# VL53L0X_ToF_Sensor.net
KiCad netlist of a schematic drawn in EAGLE
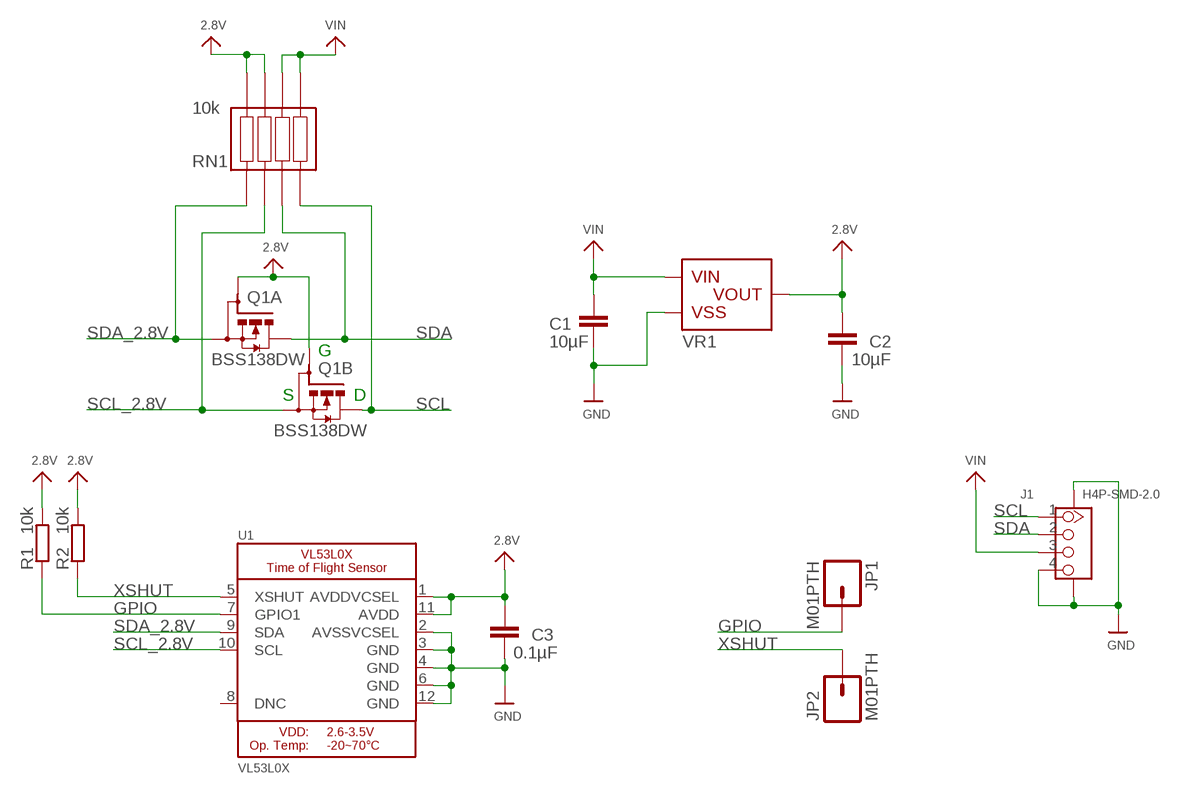
[diagram p0: schematic, sheet 1]

(export (version "E")
  (design (tool "Eeschema 10.0.6"))
  (components
    (comp (ref "C1")
      (value "10µF")
      (footprint "eagle-import:C0603")
      (libsource (lib "eagle-import") (part "C-EUC0603"))
    )
    (comp (ref "C2")
      (value "10µF")
      (footprint "eagle-import:C0603")
      (libsource (lib "eagle-import") (part "C-EUC0603"))
    )
    (comp (ref "C3")
      (value "0.1µF")
      (footprint "eagle-import:C0603")
      (libsource (lib "eagle-import") (part "C-EUC0603"))
    )
    (comp (ref "J1")
      (value "H4P-SMD-2.0")
      (footprint "eagle-import:HW4-SMD-2.0")
      (libsource (lib "eagle-import") (part "GROVE-CONNECTOR-4PIN"))
    )
    (comp (ref "JP1")
      (value "M01PTH")
      (footprint "eagle-import:1X01")
      (libsource (lib "eagle-import") (part "M01PTH"))
    )
    (comp (ref "JP2")
      (value "M01PTH")
      (footprint "eagle-import:1X01")
      (libsource (lib "eagle-import") (part "M01PTH"))
    )
    (comp (ref "Q1")
      (value "BSS138DW")
      (footprint "eagle-import:SOT363")
      (fields (field (name "MF") "ON SEMICONDUCTOR") (field (name "MPN") "NTJD5121NT1G"))
      (libsource (lib "eagle-import") (part "BSS138DW"))
    )
    (comp (ref "R1")
      (value "10k")
      (footprint "eagle-import:R0603")
      (libsource (lib "eagle-import") (part "R-EU_R0603"))
    )
    (comp (ref "R2")
      (value "10k")
      (footprint "eagle-import:R0603")
      (libsource (lib "eagle-import") (part "R-EU_R0603"))
    )
    (comp (ref "RN1")
      (value "10k")
      (footprint "eagle-import:CAY1647R0F4LF")
      (fields
        (field (name "MANUFACTURER_PART_NUMBER") "CAY16-221J4AS")
        (field (name "MOUSER_PART_NUMBER") "652-CAY16-221J4AS")
      )
      (libsource (lib "eagle-import") (part "CAY16-221J4AS"))
    )
    (comp (ref "U1")
      (value "VL53L0X")
      (footprint "eagle-import:LGA12_ST")
      (libsource (lib "eagle-import") (part "VL53L0X"))
    )
    (comp (ref "VR1")
      (value "UMW_XC6206SOT23-3")
      (footprint "eagle-import:SOT23-3")
      (libsource (lib "eagle-import") (part "UMW_XC6206SOT23-3"))
    )
  )
  (nets
    (net (code "1") (name "/GPIO") (class "Default")
      (node (ref "JP1") (pin "1") (pinfunction "1_1") (pintype "passive"))
      (node (ref "R1") (pin "1") (pinfunction "1_1") (pintype "passive"))
      (node (ref "U1") (pin "7") (pinfunction "GPIO1_7") (pintype "output"))
    )
    (net (code "2") (name "/SCL") (class "Default")
      (node (ref "J1") (pin "1") (pinfunction "1_1") (pintype "bidirectional"))
      (node (ref "Q1") (pin "3") (pinfunction "D_3") (pintype "passive"))
      (node (ref "RN1") (pin "8") (pinfunction "R1_2_8") (pintype "bidirectional"))
    )
    (net (code "3") (name "/SCL_2.8V") (class "Default")
      (node (ref "Q1") (pin "4") (pinfunction "S_4") (pintype "passive"))
      (node (ref "RN1") (pin "6") (pinfunction "R3_2_6") (pintype "bidirectional"))
      (node (ref "U1") (pin "10") (pinfunction "SCL_10") (pintype "open_collector"))
    )
    (net (code "4") (name "/SDA") (class "Default")
      (node (ref "J1") (pin "2") (pinfunction "2_2") (pintype "bidirectional"))
      (node (ref "Q1") (pin "6") (pinfunction "D_6") (pintype "passive"))
      (node (ref "RN1") (pin "7") (pinfunction "R2_2_7") (pintype "bidirectional"))
    )
    (net (code "5") (name "/SDA_2.8V") (class "Default")
      (node (ref "Q1") (pin "1") (pinfunction "S_1") (pintype "passive"))
      (node (ref "RN1") (pin "5") (pinfunction "R4_2_5") (pintype "bidirectional"))
      (node (ref "U1") (pin "9") (pinfunction "SDA_9") (pintype "open_collector"))
    )
    (net (code "6") (name "/XSHUT") (class "Default")
      (node (ref "JP2") (pin "1") (pinfunction "1_1") (pintype "passive"))
      (node (ref "R2") (pin "1") (pinfunction "1_1") (pintype "passive"))
      (node (ref "U1") (pin "5") (pinfunction "XSHUT_5") (pintype "input"))
    )
    (net (code "7") (name "2.8V") (class "Default")
      (node (ref "C2") (pin "1") (pinfunction "1_1") (pintype "passive"))
      (node (ref "C3") (pin "1") (pinfunction "1_1") (pintype "passive"))
      (node (ref "Q1") (pin "2") (pinfunction "G_2") (pintype "passive"))
      (node (ref "Q1") (pin "5") (pinfunction "G_5") (pintype "passive"))
      (node (ref "R1") (pin "2") (pinfunction "2_2") (pintype "passive"))
      (node (ref "R2") (pin "2") (pinfunction "2_2") (pintype "passive"))
      (node (ref "RN1") (pin "3") (pinfunction "R3_1_3") (pintype "bidirectional"))
      (node (ref "RN1") (pin "4") (pinfunction "R4_1_4") (pintype "bidirectional"))
      (node (ref "U1") (pin "1") (pinfunction "AVDDVCSEL_1") (pintype "power_in"))
      (node (ref "U1") (pin "11") (pinfunction "AVDD_11") (pintype "power_in"))
      (node (ref "VR1") (pin "2") (pinfunction "VOUT_2") (pintype "passive"))
    )
    (net (code "8") (name "GND") (class "Default")
      (node (ref "C1") (pin "2") (pinfunction "2_2") (pintype "passive"))
      (node (ref "C2") (pin "2") (pinfunction "2_2") (pintype "passive"))
      (node (ref "C3") (pin "2") (pinfunction "2_2") (pintype "passive"))
      (node (ref "J1") (pin "4") (pinfunction "4_4") (pintype "bidirectional"))
      (node (ref "J1") (pin "SS1") (pinfunction "SS1_SS1") (pintype "bidirectional"))
      (node (ref "J1") (pin "SS2") (pinfunction "SS2_SS2") (pintype "bidirectional"))
      (node (ref "U1") (pin "12") (pinfunction "GND_12") (pintype "power_in"))
      (node (ref "U1") (pin "2") (pinfunction "AVSSVCSEL_2") (pintype "power_in"))
      (node (ref "U1") (pin "3") (pinfunction "GND_3") (pintype "power_in"))
      (node (ref "U1") (pin "4") (pinfunction "GND_4") (pintype "power_in"))
      (node (ref "U1") (pin "6") (pinfunction "GND_6") (pintype "power_in"))
      (node (ref "VR1") (pin "1") (pinfunction "VSS_1") (pintype "passive"))
    )
    (net (code "9") (name "VIN") (class "Default")
      (node (ref "C1") (pin "1") (pinfunction "1_1") (pintype "passive"))
      (node (ref "J1") (pin "3") (pinfunction "3_3") (pintype "bidirectional"))
      (node (ref "RN1") (pin "1") (pinfunction "R1_1_1") (pintype "bidirectional"))
      (node (ref "RN1") (pin "2") (pinfunction "R2_1_2") (pintype "bidirectional"))
      (node (ref "VR1") (pin "3") (pinfunction "VIN_3") (pintype "passive"))
    )
    (net (code "10") (name "unconnected-(U1-DNC-Pad8)") (class "Default")
      (node (ref "U1") (pin "8") (pinfunction "DNC_8") (pintype "no_connect"))
    )
  )
)
